# Althium_Schematic.net
KiCad netlist of a schematic drawn in Altium Designer
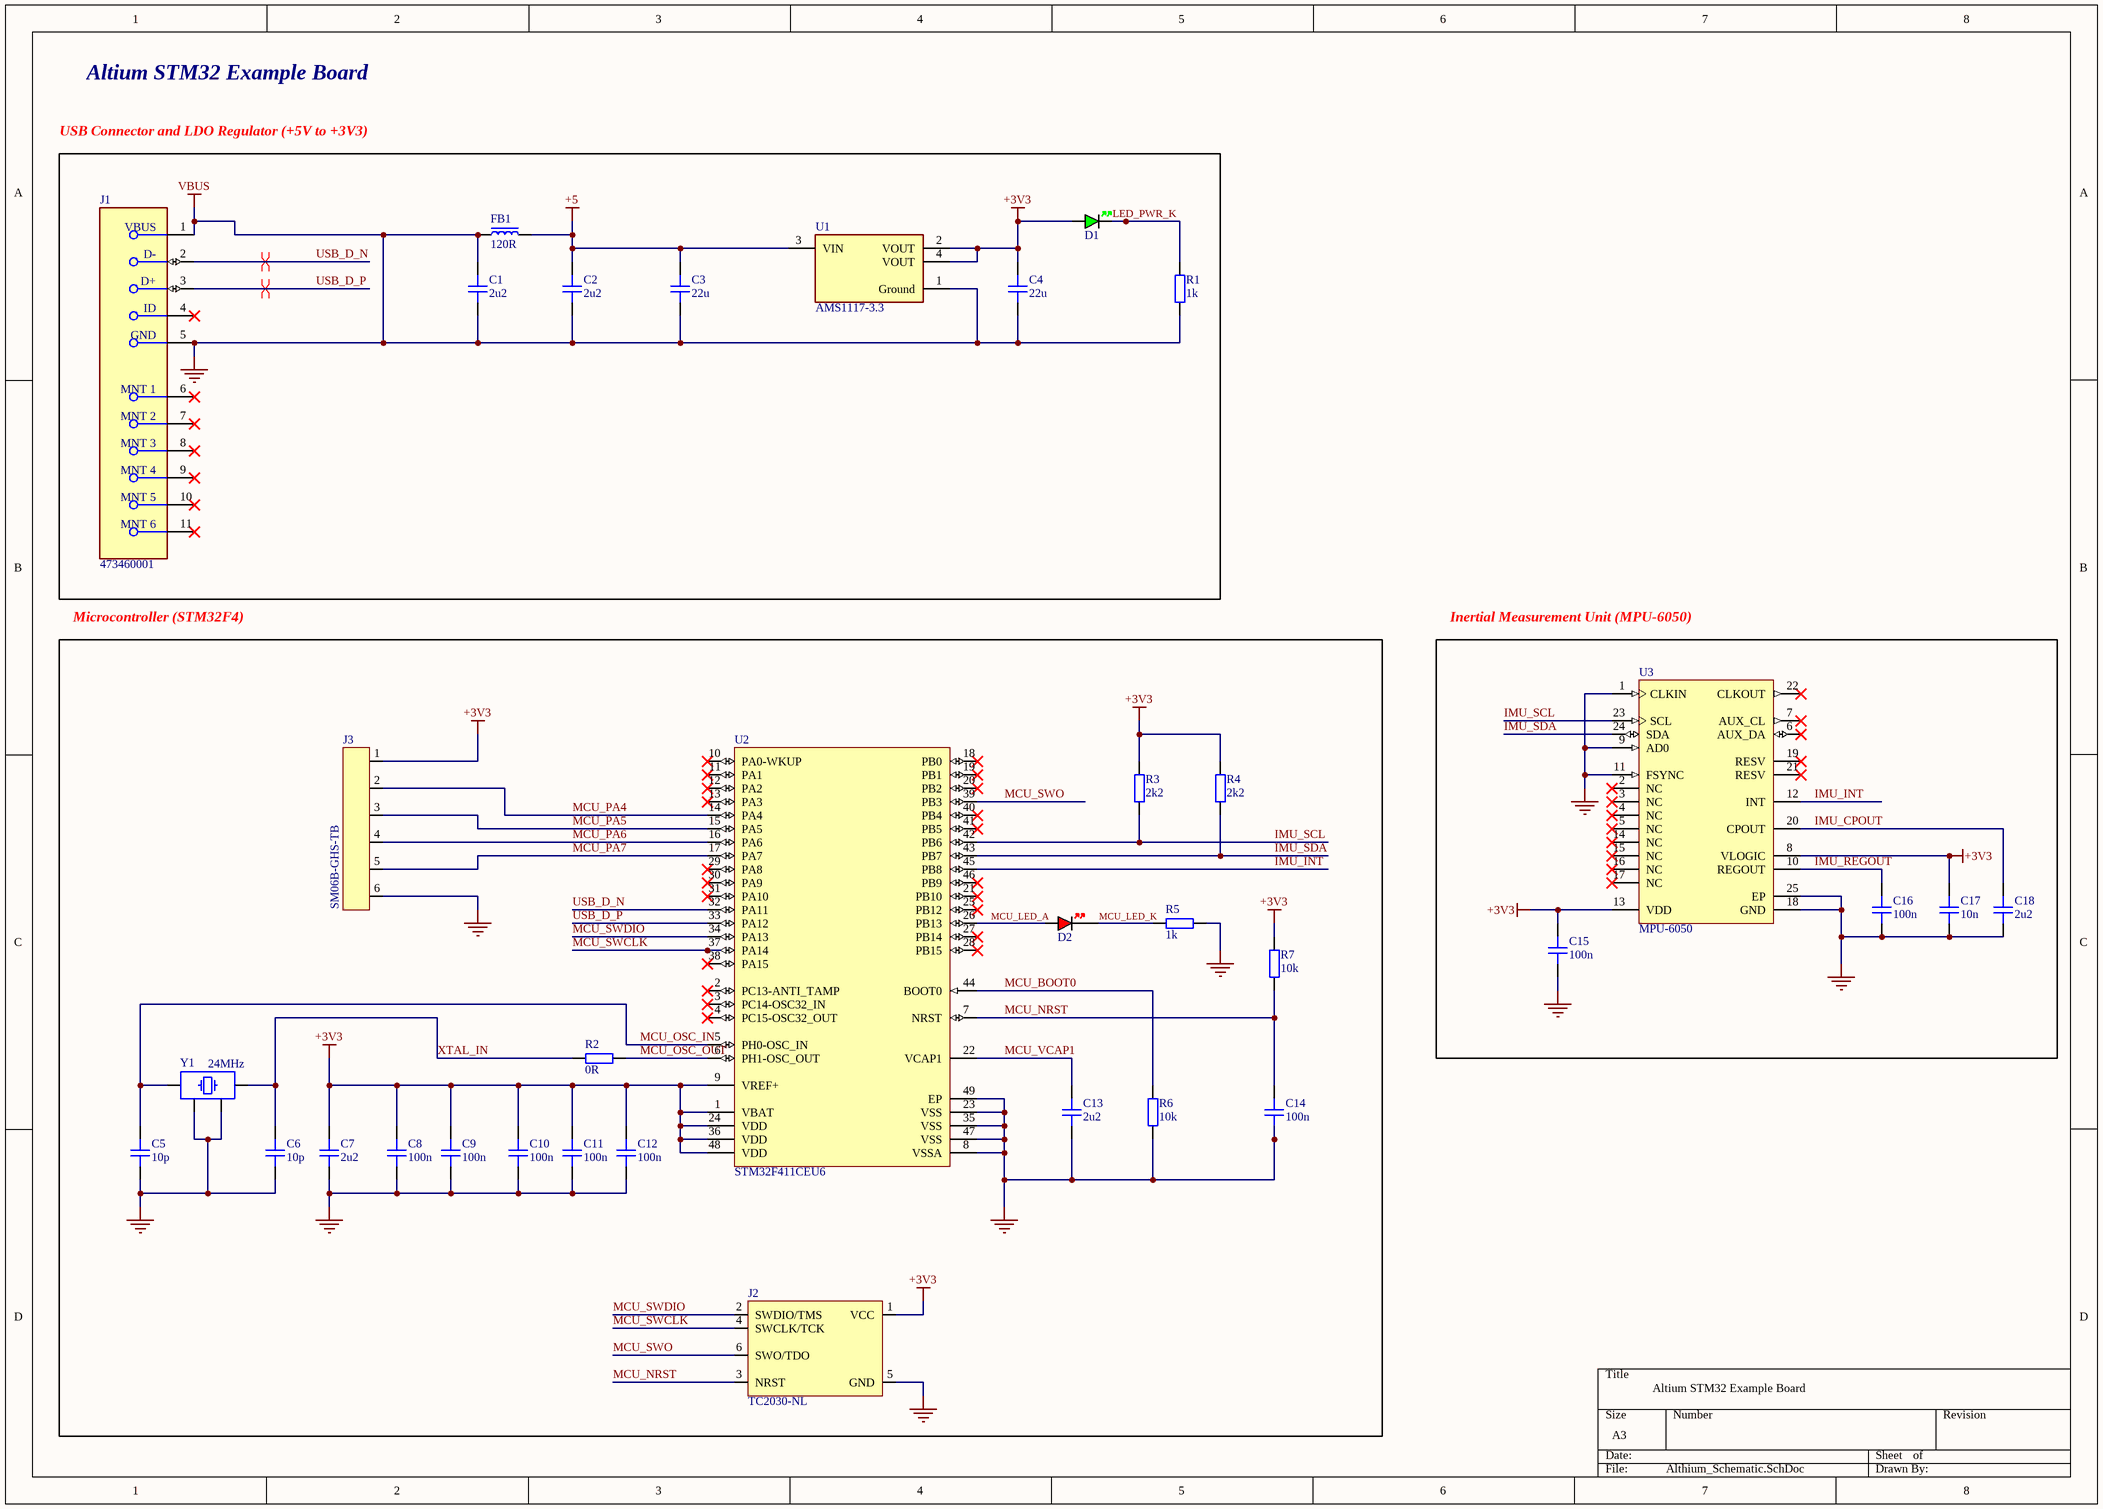
[diagram p0: Althium_Schematic.SchDoc]

(export (version "E")
  (design (tool "Eeschema 10.0.6"))
  (components
    (comp (ref "C1")
      (value "2u2")
      (footprint "CAP_0603")
      (description "Capacitor SMD 0603 16V")
      (libsource (lib "Schematic-Lib-PhilsLab") (part "CAP_0603_16V"))
    )
    (comp (ref "C2")
      (value "2u2")
      (footprint "CAP_0603")
      (description "Capacitor SMD 0603 16V")
      (libsource (lib "Schematic-Lib-PhilsLab") (part "CAP_0603_16V"))
    )
    (comp (ref "C3")
      (value "22u")
      (footprint "CAP_0805")
      (description "Capacitor SMD 0805 16V")
      (libsource (lib "Schematic-Lib-PhilsLab") (part "CAP_0805_16V"))
    )
    (comp (ref "C4")
      (value "22u")
      (footprint "CAP_0805")
      (description "Capacitor SMD 0805 16V")
      (libsource (lib "Schematic-Lib-PhilsLab") (part "CAP_0805_16V"))
    )
    (comp (ref "C5")
      (value "10p")
      (footprint "CAP_0402")
      (description "Capacitor SMD 0402 16V")
      (libsource (lib "Schematic-Lib-PhilsLab") (part "CAP_0402_16V"))
    )
    (comp (ref "C6")
      (value "10p")
      (footprint "CAP_0402")
      (description "Capacitor SMD 0402 16V")
      (libsource (lib "Schematic-Lib-PhilsLab") (part "CAP_0402_16V"))
    )
    (comp (ref "C7")
      (value "2u2")
      (footprint "CAP_0603")
      (description "Capacitor SMD 0603 16V")
      (libsource (lib "Schematic-Lib-PhilsLab") (part "CAP_0603_16V"))
    )
    (comp (ref "C8")
      (value "100n")
      (footprint "CAP_0402")
      (description "Capacitor SMD 0402 16V")
      (libsource (lib "Schematic-Lib-PhilsLab") (part "CAP_0402_16V"))
    )
    (comp (ref "C9")
      (value "100n")
      (footprint "CAP_0402")
      (description "Capacitor SMD 0402 16V")
      (libsource (lib "Schematic-Lib-PhilsLab") (part "CAP_0402_16V"))
    )
    (comp (ref "C10")
      (value "100n")
      (footprint "CAP_0402")
      (description "Capacitor SMD 0402 16V")
      (libsource (lib "Schematic-Lib-PhilsLab") (part "CAP_0402_16V"))
    )
    (comp (ref "C11")
      (value "100n")
      (footprint "CAP_0402")
      (description "Capacitor SMD 0402 16V")
      (libsource (lib "Schematic-Lib-PhilsLab") (part "CAP_0402_16V"))
    )
    (comp (ref "C12")
      (value "100n")
      (footprint "CAP_0402")
      (description "Capacitor SMD 0402 16V")
      (libsource (lib "Schematic-Lib-PhilsLab") (part "CAP_0402_16V"))
    )
    (comp (ref "C13")
      (value "2u2")
      (footprint "CAP_0603")
      (description "Capacitor SMD 0603 16V")
      (libsource (lib "Schematic-Lib-PhilsLab") (part "CAP_0603_16V"))
    )
    (comp (ref "C14")
      (value "100n")
      (footprint "CAP_0402")
      (description "Capacitor SMD 0402 16V")
      (libsource (lib "Schematic-Lib-PhilsLab") (part "CAP_0402_16V"))
    )
    (comp (ref "C15")
      (value "100n")
      (footprint "CAP_0402")
      (description "Capacitor SMD 0402 16V")
      (libsource (lib "Schematic-Lib-PhilsLab") (part "CAP_0402_16V"))
    )
    (comp (ref "C16")
      (value "100n")
      (footprint "CAP_0402")
      (description "Capacitor SMD 0402 16V")
      (libsource (lib "Schematic-Lib-PhilsLab") (part "CAP_0402_16V"))
    )
    (comp (ref "C17")
      (value "10n")
      (footprint "CAP_0402")
      (description "Capacitor SMD 0402 16V")
      (libsource (lib "Schematic-Lib-PhilsLab") (part "CAP_0402_16V"))
    )
    (comp (ref "C18")
      (value "2u2")
      (footprint "CAP_0603")
      (description "Capacitor SMD 0603 16V")
      (libsource (lib "Schematic-Lib-PhilsLab") (part "CAP_0603_16V"))
    )
    (comp (ref "D1")
      (value "GREEN")
      (footprint "LED_0402_GREEN")
      (description "LED 0402 GREEN SMD")
      (libsource (lib "Schematic-Lib-PhilsLab") (part "LED_0402_GREEN"))
    )
    (comp (ref "D2")
      (value "RED")
      (footprint "LED_0402_RED")
      (description "LED 0402 RED SMD")
      (libsource (lib "Schematic-Lib-PhilsLab") (part "LED_0402_RED"))
    )
    (comp (ref "FB1")
      (value "120R")
      (footprint "FB_0603")
      (description "Ferrite Bead SMD 0603")
      (libsource (lib "Schematic-Lib-PhilsLab") (part "FB_0603"))
    )
    (comp (ref "J1")
      (value "473460001")
      (footprint "FP-473460001-MFG")
      (description "USB - micro B USB 2.0 Receptacle Connector 5 Position Surface Mount, Right Angle")
      (fields (field (name "OCTOPART") "https://octopart.com/47346-0001-molex-7164928"))
      (libsource (lib "Altium Content Vault") (part "53ae1f1d9b557310b43ca686e5bb76a"))
    )
    (comp (ref "J2")
      (value "TC2030-NL")
      (footprint "TC2030-NL-FP")
      (description "Tag-Connect No-Solder SWD Debug Connector (No Legs) DO NOT PLACE")
      (fields
        (field (name "MANUFACTURER") "Tag-Connect")
        (field (name "MANUFACTURER PART NUMBER") "TC2030-NL-FP")
      )
      (libsource (lib "Schematic-Lib-PhilsLab") (part "TC2030-NL"))
    )
    (comp (ref "J3")
      (value "SM06B-GHS-TB")
      (footprint "SM06B-GHS-TB")
      (description "Header Connector 6 Position 1.25MM Pitch SMD Horizontal JST GH")
      (fields (field (name "MANUFACTURER") "JST"))
      (libsource (lib "Schematic-Lib-PhilsLab") (part "SM06B-GHS-TB"))
    )
    (comp (ref "R1")
      (value "1k")
      (footprint "RES_0402")
      (description "Resistor SMD 0402")
      (libsource (lib "Schematic-Lib-PhilsLab") (part "RES_0402"))
    )
    (comp (ref "R2")
      (value "0R")
      (footprint "RES_0402")
      (description "Resistor SMD 0402")
      (libsource (lib "Schematic-Lib-PhilsLab") (part "RES_0402"))
    )
    (comp (ref "R3")
      (value "2k2")
      (footprint "RES_0402")
      (description "Resistor SMD 0402")
      (libsource (lib "Schematic-Lib-PhilsLab") (part "RES_0402"))
    )
    (comp (ref "R4")
      (value "2k2")
      (footprint "RES_0402")
      (description "Resistor SMD 0402")
      (libsource (lib "Schematic-Lib-PhilsLab") (part "RES_0402"))
    )
    (comp (ref "R5")
      (value "1k")
      (footprint "RES_0402")
      (description "Resistor SMD 0402")
      (libsource (lib "Schematic-Lib-PhilsLab") (part "RES_0402"))
    )
    (comp (ref "R6")
      (value "10k")
      (footprint "RES_0402")
      (description "Resistor SMD 0402")
      (libsource (lib "Schematic-Lib-PhilsLab") (part "RES_0402"))
    )
    (comp (ref "R7")
      (value "10k")
      (footprint "RES_0402")
      (description "Resistor SMD 0402")
      (libsource (lib "Schematic-Lib-PhilsLab") (part "RES_0402"))
    )
    (comp (ref "U1")
      (value "AMS1117-3.3")
      (footprint "FP-AMS1117-IPC_C")
      (description "LDO Voltage Regulators 1A, 3.3V")
      (fields
        (field (name "OCTOPART") "https://octopart.com/ams1117-3.3-advanced+monolithic+systems-25899300")
        (field (name "MANUFACTURER") "Advanced Monolithic Systems")
      )
      (libsource (lib "Altium Content Vault") (part "8bdbb5f8e77002000e30dd2845d0354"))
    )
    (comp (ref "U2")
      (value "STM32F411CEU6")
      (footprint "STM-UFQFPN48_L")
      (libsource (lib "Altium Content Vault") (part "MC-ARM-STM32F411-UFQFPN48"))
    )
    (comp (ref "U3")
      (value "MPU-6050")
      (footprint "IS-QFN-24_V")
      (fields (field (name "MANUFACTURER") "InvenSense"))
      (libsource (lib "Altium Content Vault") (part "IS-MPU-6050-QFN-24"))
    )
    (comp (ref "Y1")
      (value "24MHz")
      (footprint "XTAL_3225")
      (description "Crystal SMD 24MHz 10PPM 7pF 3225")
      (fields (field (name "MANUFACTURER") "Epson"))
      (libsource (lib "Schematic-Lib-PhilsLab") (part "TSX-3225_24.0000MF15X-AC"))
    )
  )
  (nets
    (net (code "1") (name "+3V3") (class "Default")
      (node (ref "C10") (pin "2") (pinfunction "2_2") (pintype "passive"))
      (node (ref "C11") (pin "2") (pinfunction "2_2") (pintype "passive"))
      (node (ref "C12") (pin "2") (pinfunction "2_2") (pintype "passive"))
      (node (ref "C15") (pin "2") (pinfunction "2_2") (pintype "passive"))
      (node (ref "C17") (pin "2") (pinfunction "2_2") (pintype "passive"))
      (node (ref "C4") (pin "2") (pinfunction "2_2") (pintype "passive"))
      (node (ref "C7") (pin "2") (pinfunction "2_2") (pintype "passive"))
      (node (ref "C8") (pin "2") (pinfunction "2_2") (pintype "passive"))
      (node (ref "C9") (pin "2") (pinfunction "2_2") (pintype "passive"))
      (node (ref "D1") (pin "A") (pinfunction "A_A") (pintype "passive"))
      (node (ref "J2") (pin "1") (pinfunction "VCC_1") (pintype "passive"))
      (node (ref "J3") (pin "1") (pinfunction "1_1") (pintype "passive"))
      (node (ref "R3") (pin "2") (pinfunction "2_2") (pintype "passive"))
      (node (ref "R4") (pin "2") (pinfunction "2_2") (pintype "passive"))
      (node (ref "R7") (pin "2") (pinfunction "2_2") (pintype "passive"))
      (node (ref "U1") (pin "2") (pinfunction "VOUT_2") (pintype "passive"))
      (node (ref "U1") (pin "4") (pinfunction "VOUT_4") (pintype "passive"))
      (node (ref "U2") (pin "1") (pinfunction "VBAT_1") (pintype "power_in"))
      (node (ref "U2") (pin "24") (pinfunction "VDD_24") (pintype "power_in"))
      (node (ref "U2") (pin "36") (pinfunction "VDD_36") (pintype "power_in"))
      (node (ref "U2") (pin "48") (pinfunction "VDD_48") (pintype "power_in"))
      (node (ref "U2") (pin "9") (pinfunction "VREF+_9") (pintype "power_in"))
      (node (ref "U3") (pin "13") (pinfunction "VDD_13") (pintype "power_in"))
      (node (ref "U3") (pin "8") (pinfunction "VLOGIC_8") (pintype "power_in"))
    )
    (net (code "2") (name "+5") (class "Default")
      (node (ref "C2") (pin "2") (pinfunction "2_2") (pintype "passive"))
      (node (ref "C3") (pin "2") (pinfunction "2_2") (pintype "passive"))
      (node (ref "FB1") (pin "2") (pinfunction "2_2") (pintype "passive"))
      (node (ref "U1") (pin "3") (pinfunction "VIN_3") (pintype "power_in"))
    )
    (net (code "3") (name "/IMU_CPOUT") (class "Default")
      (node (ref "C18") (pin "2") (pinfunction "2_2") (pintype "passive"))
      (node (ref "U3") (pin "20") (pinfunction "CPOUT_20") (pintype "passive"))
    )
    (net (code "4") (name "/IMU_INT") (class "Default")
      (node (ref "U2") (pin "45") (pinfunction "PB8_45") (pintype "bidirectional"))
      (node (ref "U3") (pin "12") (pinfunction "INT_12") (pintype "open_collector"))
    )
    (net (code "5") (name "/IMU_REGOUT") (class "Default")
      (node (ref "C16") (pin "2") (pinfunction "2_2") (pintype "passive"))
      (node (ref "U3") (pin "10") (pinfunction "REGOUT_10") (pintype "passive"))
    )
    (net (code "6") (name "/IMU_SCL") (class "Default")
      (node (ref "R3") (pin "1") (pinfunction "1_1") (pintype "passive"))
      (node (ref "U2") (pin "42") (pinfunction "PB6_42") (pintype "bidirectional"))
      (node (ref "U3") (pin "23") (pinfunction "SCL_23") (pintype "input"))
    )
    (net (code "7") (name "/IMU_SDA") (class "Default")
      (node (ref "R4") (pin "1") (pinfunction "1_1") (pintype "passive"))
      (node (ref "U2") (pin "43") (pinfunction "PB7_43") (pintype "bidirectional"))
      (node (ref "U3") (pin "24") (pinfunction "SDA_24") (pintype "bidirectional"))
    )
    (net (code "8") (name "/LED_PWR_K") (class "Default")
      (node (ref "D1") (pin "K") (pinfunction "K_K") (pintype "passive"))
      (node (ref "R1") (pin "2") (pinfunction "2_2") (pintype "passive"))
    )
    (net (code "9") (name "/MCU_BOOT0") (class "Default")
      (node (ref "R6") (pin "2") (pinfunction "2_2") (pintype "passive"))
      (node (ref "U2") (pin "44") (pinfunction "BOOT0_44") (pintype "input"))
    )
    (net (code "10") (name "/MCU_LED_A") (class "Default")
      (node (ref "D2") (pin "A") (pinfunction "A_A") (pintype "passive"))
      (node (ref "U2") (pin "26") (pinfunction "PB13_26") (pintype "bidirectional"))
    )
    (net (code "11") (name "/MCU_LED_K") (class "Default")
      (node (ref "D2") (pin "K") (pinfunction "K_K") (pintype "passive"))
      (node (ref "R5") (pin "2") (pinfunction "2_2") (pintype "passive"))
    )
    (net (code "12") (name "/MCU_NRST") (class "Default")
      (node (ref "C14") (pin "2") (pinfunction "2_2") (pintype "passive"))
      (node (ref "J2") (pin "3") (pinfunction "NRST_3") (pintype "passive"))
      (node (ref "R7") (pin "1") (pinfunction "1_1") (pintype "passive"))
      (node (ref "U2") (pin "7") (pinfunction "NRST_7") (pintype "bidirectional"))
    )
    (net (code "13") (name "/MCU_OSC_IN") (class "Default")
      (node (ref "C5") (pin "2") (pinfunction "2_2") (pintype "passive"))
      (node (ref "U2") (pin "5") (pinfunction "PH0-OSC_IN_5") (pintype "bidirectional"))
      (node (ref "Y1") (pin "1") (pinfunction "1_1") (pintype "passive"))
    )
    (net (code "14") (name "/MCU_OSC_OUT") (class "Default")
      (node (ref "R2") (pin "2") (pinfunction "2_2") (pintype "passive"))
      (node (ref "U2") (pin "6") (pinfunction "PH1-OSC_OUT_6") (pintype "bidirectional"))
    )
    (net (code "15") (name "/MCU_PA4") (class "Default")
      (node (ref "J3") (pin "2") (pinfunction "2_2") (pintype "passive"))
      (node (ref "U2") (pin "14") (pinfunction "PA4_14") (pintype "bidirectional"))
    )
    (net (code "16") (name "/MCU_PA5") (class "Default")
      (node (ref "J3") (pin "3") (pinfunction "3_3") (pintype "passive"))
      (node (ref "U2") (pin "15") (pinfunction "PA5_15") (pintype "bidirectional"))
    )
    (net (code "17") (name "/MCU_PA6") (class "Default")
      (node (ref "J3") (pin "4") (pinfunction "4_4") (pintype "passive"))
      (node (ref "U2") (pin "16") (pinfunction "PA6_16") (pintype "bidirectional"))
    )
    (net (code "18") (name "/MCU_PA7") (class "Default")
      (node (ref "J3") (pin "5") (pinfunction "5_5") (pintype "passive"))
      (node (ref "U2") (pin "17") (pinfunction "PA7_17") (pintype "bidirectional"))
    )
    (net (code "19") (name "/MCU_SWCLK") (class "Default")
      (node (ref "J2") (pin "4") (pinfunction "SWCLK/TCK_4") (pintype "passive"))
      (node (ref "U2") (pin "37") (pinfunction "PA14_37") (pintype "bidirectional"))
    )
    (net (code "20") (name "/MCU_SWDIO") (class "Default")
      (node (ref "J2") (pin "2") (pinfunction "SWDIO/TMS_2") (pintype "passive"))
      (node (ref "U2") (pin "34") (pinfunction "PA13_34") (pintype "bidirectional"))
    )
    (net (code "21") (name "/MCU_SWO") (class "Default")
      (node (ref "J2") (pin "6") (pinfunction "SWO/TDO_6") (pintype "passive"))
      (node (ref "U2") (pin "39") (pinfunction "PB3_39") (pintype "bidirectional"))
    )
    (net (code "22") (name "/MCU_VCAP1") (class "Default")
      (node (ref "C13") (pin "2") (pinfunction "2_2") (pintype "passive"))
      (node (ref "U2") (pin "22") (pinfunction "VCAP1_22") (pintype "passive"))
    )
    (net (code "23") (name "/USB_D_N") (class "Default")
      (node (ref "J1") (pin "2") (pinfunction "D-_2") (pintype "bidirectional"))
      (node (ref "U2") (pin "32") (pinfunction "PA11_32") (pintype "bidirectional"))
    )
    (net (code "24") (name "/USB_D_P") (class "Default")
      (node (ref "J1") (pin "3") (pinfunction "D+_3") (pintype "bidirectional"))
      (node (ref "U2") (pin "33") (pinfunction "PA12_33") (pintype "bidirectional"))
    )
    (net (code "25") (name "/XTAL_IN") (class "Default")
      (node (ref "C6") (pin "2") (pinfunction "2_2") (pintype "passive"))
      (node (ref "R2") (pin "1") (pinfunction "1_1") (pintype "passive"))
      (node (ref "Y1") (pin "3") (pinfunction "3_3") (pintype "passive"))
    )
    (net (code "26") (name "GND") (class "Default")
      (node (ref "C1") (pin "1") (pinfunction "1_1") (pintype "passive"))
      (node (ref "C1") (pin "2") (pinfunction "2_2") (pintype "passive"))
      (node (ref "C10") (pin "1") (pinfunction "1_1") (pintype "passive"))
      (node (ref "C11") (pin "1") (pinfunction "1_1") (pintype "passive"))
      (node (ref "C12") (pin "1") (pinfunction "1_1") (pintype "passive"))
      (node (ref "C13") (pin "1") (pinfunction "1_1") (pintype "passive"))
      (node (ref "C14") (pin "1") (pinfunction "1_1") (pintype "passive"))
      (node (ref "C15") (pin "1") (pinfunction "1_1") (pintype "passive"))
      (node (ref "C16") (pin "1") (pinfunction "1_1") (pintype "passive"))
      (node (ref "C17") (pin "1") (pinfunction "1_1") (pintype "passive"))
      (node (ref "C18") (pin "1") (pinfunction "1_1") (pintype "passive"))
      (node (ref "C2") (pin "1") (pinfunction "1_1") (pintype "passive"))
      (node (ref "C3") (pin "1") (pinfunction "1_1") (pintype "passive"))
      (node (ref "C4") (pin "1") (pinfunction "1_1") (pintype "passive"))
      (node (ref "C5") (pin "1") (pinfunction "1_1") (pintype "passive"))
      (node (ref "C6") (pin "1") (pinfunction "1_1") (pintype "passive"))
      (node (ref "C7") (pin "1") (pinfunction "1_1") (pintype "passive"))
      (node (ref "C8") (pin "1") (pinfunction "1_1") (pintype "passive"))
      (node (ref "C9") (pin "1") (pinfunction "1_1") (pintype "passive"))
      (node (ref "FB1") (pin "1") (pinfunction "1_1") (pintype "passive"))
      (node (ref "J1") (pin "1") (pinfunction "VBUS_1") (pintype "power_in"))
      (node (ref "J1") (pin "5") (pinfunction "GND_5") (pintype "power_in"))
      (node (ref "J2") (pin "5") (pinfunction "GND_5") (pintype "passive"))
      (node (ref "J3") (pin "6") (pinfunction "6_6") (pintype "passive"))
      (node (ref "R1") (pin "1") (pinfunction "1_1") (pintype "passive"))
      (node (ref "R5") (pin "1") (pinfunction "1_1") (pintype "passive"))
      (node (ref "R6") (pin "1") (pinfunction "1_1") (pintype "passive"))
      (node (ref "U1") (pin "1") (pinfunction "Ground_1") (pintype "power_in"))
      (node (ref "U2") (pin "23") (pinfunction "VSS_23") (pintype "power_in"))
      (node (ref "U2") (pin "35") (pinfunction "VSS_35") (pintype "power_in"))
      (node (ref "U2") (pin "47") (pinfunction "VSS_47") (pintype "power_in"))
      (node (ref "U2") (pin "49") (pinfunction "EP_49") (pintype "power_in"))
      (node (ref "U2") (pin "8") (pinfunction "VSSA_8") (pintype "power_in"))
      (node (ref "U3") (pin "1") (pinfunction "CLKIN_1") (pintype "input"))
      (node (ref "U3") (pin "11") (pinfunction "FSYNC_11") (pintype "input"))
      (node (ref "U3") (pin "18") (pinfunction "GND_18") (pintype "power_in"))
      (node (ref "U3") (pin "25") (pinfunction "EP_25") (pintype "power_in"))
      (node (ref "U3") (pin "9") (pinfunction "AD0_9") (pintype "input"))
      (node (ref "Y1") (pin "2") (pinfunction "2_2") (pintype "passive"))
      (node (ref "Y1") (pin "4") (pinfunction "4_4") (pintype "passive"))
    )
    (net (code "27") (name "unconnected-(J1-ID-Pad4)") (class "Default")
      (node (ref "J1") (pin "4") (pinfunction "ID_4") (pintype "passive+no_connect"))
    )
    (net (code "28") (name "unconnected-(J1-MNT_1-Pad6)") (class "Default")
      (node (ref "J1") (pin "6") (pinfunction "MNT_1_6") (pintype "passive+no_connect"))
    )
    (net (code "29") (name "unconnected-(J1-MNT_2-Pad7)") (class "Default")
      (node (ref "J1") (pin "7") (pinfunction "MNT_2_7") (pintype "passive+no_connect"))
    )
    (net (code "30") (name "unconnected-(J1-MNT_3-Pad8)") (class "Default")
      (node (ref "J1") (pin "8") (pinfunction "MNT_3_8") (pintype "passive+no_connect"))
    )
    (net (code "31") (name "unconnected-(J1-MNT_4-Pad9)") (class "Default")
      (node (ref "J1") (pin "9") (pinfunction "MNT_4_9") (pintype "passive+no_connect"))
    )
    (net (code "32") (name "unconnected-(J1-MNT_5-Pad10)") (class "Default")
      (node (ref "J1") (pin "10") (pinfunction "MNT_5_10") (pintype "passive+no_connect"))
    )
    (net (code "33") (name "unconnected-(J1-MNT_6-Pad11)") (class "Default")
      (node (ref "J1") (pin "11") (pinfunction "MNT_6_11") (pintype "passive+no_connect"))
    )
    (net (code "34") (name "unconnected-(U2-PA0-WKUP-Pad10)") (class "Default")
      (node (ref "U2") (pin "10") (pinfunction "PA0-WKUP_10") (pintype "bidirectional+no_connect"))
    )
    (net (code "35") (name "unconnected-(U2-PA1-Pad11)") (class "Default")
      (node (ref "U2") (pin "11") (pinfunction "PA1_11") (pintype "bidirectional+no_connect"))
    )
    (net (code "36") (name "unconnected-(U2-PA2-Pad12)") (class "Default")
      (node (ref "U2") (pin "12") (pinfunction "PA2_12") (pintype "bidirectional+no_connect"))
    )
    (net (code "37") (name "unconnected-(U2-PA3-Pad13)") (class "Default")
      (node (ref "U2") (pin "13") (pinfunction "PA3_13") (pintype "bidirectional+no_connect"))
    )
    (net (code "38") (name "unconnected-(U2-PA8-Pad29)") (class "Default")
      (node (ref "U2") (pin "29") (pinfunction "PA8_29") (pintype "bidirectional+no_connect"))
    )
    (net (code "39") (name "unconnected-(U2-PA9-Pad30)") (class "Default")
      (node (ref "U2") (pin "30") (pinfunction "PA9_30") (pintype "bidirectional+no_connect"))
    )
    (net (code "40") (name "unconnected-(U2-PA10-Pad31)") (class "Default")
      (node (ref "U2") (pin "31") (pinfunction "PA10_31") (pintype "bidirectional+no_connect"))
    )
    (net (code "41") (name "unconnected-(U2-PA15-Pad38)") (class "Default")
      (node (ref "U2") (pin "38") (pinfunction "PA15_38") (pintype "bidirectional+no_connect"))
    )
    (net (code "42") (name "unconnected-(U2-PB0-Pad18)") (class "Default")
      (node (ref "U2") (pin "18") (pinfunction "PB0_18") (pintype "bidirectional+no_connect"))
    )
    (net (code "43") (name "unconnected-(U2-PB1-Pad19)") (class "Default")
      (node (ref "U2") (pin "19") (pinfunction "PB1_19") (pintype "bidirectional+no_connect"))
    )
    (net (code "44") (name "unconnected-(U2-PB2-Pad20)") (class "Default")
      (node (ref "U2") (pin "20") (pinfunction "PB2_20") (pintype "bidirectional+no_connect"))
    )
    (net (code "45") (name "unconnected-(U2-PB4-Pad40)") (class "Default")
      (node (ref "U2") (pin "40") (pinfunction "PB4_40") (pintype "bidirectional+no_connect"))
    )
    (net (code "46") (name "unconnected-(U2-PB5-Pad41)") (class "Default")
      (node (ref "U2") (pin "41") (pinfunction "PB5_41") (pintype "bidirectional+no_connect"))
    )
    (net (code "47") (name "unconnected-(U2-PB9-Pad46)") (class "Default")
      (node (ref "U2") (pin "46") (pinfunction "PB9_46") (pintype "bidirectional+no_connect"))
    )
    (net (code "48") (name "unconnected-(U2-PB10-Pad21)") (class "Default")
      (node (ref "U2") (pin "21") (pinfunction "PB10_21") (pintype "bidirectional+no_connect"))
    )
    (net (code "49") (name "unconnected-(U2-PB12-Pad25)") (class "Default")
      (node (ref "U2") (pin "25") (pinfunction "PB12_25") (pintype "bidirectional+no_connect"))
    )
    (net (code "50") (name "unconnected-(U2-PB14-Pad27)") (class "Default")
      (node (ref "U2") (pin "27") (pinfunction "PB14_27") (pintype "bidirectional+no_connect"))
    )
    (net (code "51") (name "unconnected-(U2-PB15-Pad28)") (class "Default")
      (node (ref "U2") (pin "28") (pinfunction "PB15_28") (pintype "bidirectional+no_connect"))
    )
    (net (code "52") (name "unconnected-(U2-PC13-ANTI_TAMP-Pad2)") (class "Default")
      (node (ref "U2") (pin "2") (pinfunction "PC13-ANTI_TAMP_2") (pintype "bidirectional+no_connect"))
    )
    (net (code "53") (name "unconnected-(U2-PC14-OSC32_IN-Pad3)") (class "Default")
      (node (ref "U2") (pin "3") (pinfunction "PC14-OSC32_IN_3") (pintype "bidirectional+no_connect"))
    )
    (net (code "54") (name "unconnected-(U2-PC15-OSC32_OUT-Pad4)") (class "Default")
      (node (ref "U2") (pin "4") (pinfunction "PC15-OSC32_OUT_4") (pintype "bidirectional+no_connect"))
    )
    (net (code "55") (name "unconnected-(U3-AUX_CL-Pad7)") (class "Default")
      (node (ref "U3") (pin "7") (pinfunction "AUX_CL_7") (pintype "output+no_connect"))
    )
    (net (code "56") (name "unconnected-(U3-AUX_DA-Pad6)") (class "Default")
      (node (ref "U3") (pin "6") (pinfunction "AUX_DA_6") (pintype "bidirectional+no_connect"))
    )
    (net (code "57") (name "unconnected-(U3-CLKOUT-Pad22)") (class "Default")
      (node (ref "U3") (pin "22") (pinfunction "CLKOUT_22") (pintype "output+no_connect"))
    )
    (net (code "58") (name "unconnected-(U3-NC-Pad2)") (class "Default")
      (node (ref "U3") (pin "2") (pinfunction "NC_2") (pintype "passive+no_connect"))
    )
    (net (code "59") (name "unconnected-(U3-NC-Pad3)") (class "Default")
      (node (ref "U3") (pin "3") (pinfunction "NC_3") (pintype "passive+no_connect"))
    )
    (net (code "60") (name "unconnected-(U3-NC-Pad4)") (class "Default")
      (node (ref "U3") (pin "4") (pinfunction "NC_4") (pintype "passive+no_connect"))
    )
    (net (code "61") (name "unconnected-(U3-NC-Pad5)") (class "Default")
      (node (ref "U3") (pin "5") (pinfunction "NC_5") (pintype "passive+no_connect"))
    )
    (net (code "62") (name "unconnected-(U3-NC-Pad14)") (class "Default")
      (node (ref "U3") (pin "14") (pinfunction "NC_14") (pintype "passive+no_connect"))
    )
    (net (code "63") (name "unconnected-(U3-NC-Pad15)") (class "Default")
      (node (ref "U3") (pin "15") (pinfunction "NC_15") (pintype "passive+no_connect"))
    )
    (net (code "64") (name "unconnected-(U3-NC-Pad16)") (class "Default")
      (node (ref "U3") (pin "16") (pinfunction "NC_16") (pintype "passive+no_connect"))
    )
    (net (code "65") (name "unconnected-(U3-NC-Pad17)") (class "Default")
      (node (ref "U3") (pin "17") (pinfunction "NC_17") (pintype "passive+no_connect"))
    )
    (net (code "66") (name "unconnected-(U3-RESV-Pad19)") (class "Default")
      (node (ref "U3") (pin "19") (pinfunction "RESV_19") (pintype "passive+no_connect"))
    )
    (net (code "67") (name "unconnected-(U3-RESV-Pad21)") (class "Default")
      (node (ref "U3") (pin "21") (pinfunction "RESV_21") (pintype "passive+no_connect"))
    )
  )
)
